# SiLPA_LVDS_IFC.net
KiCad netlist of a schematic drawn in Altium Designer
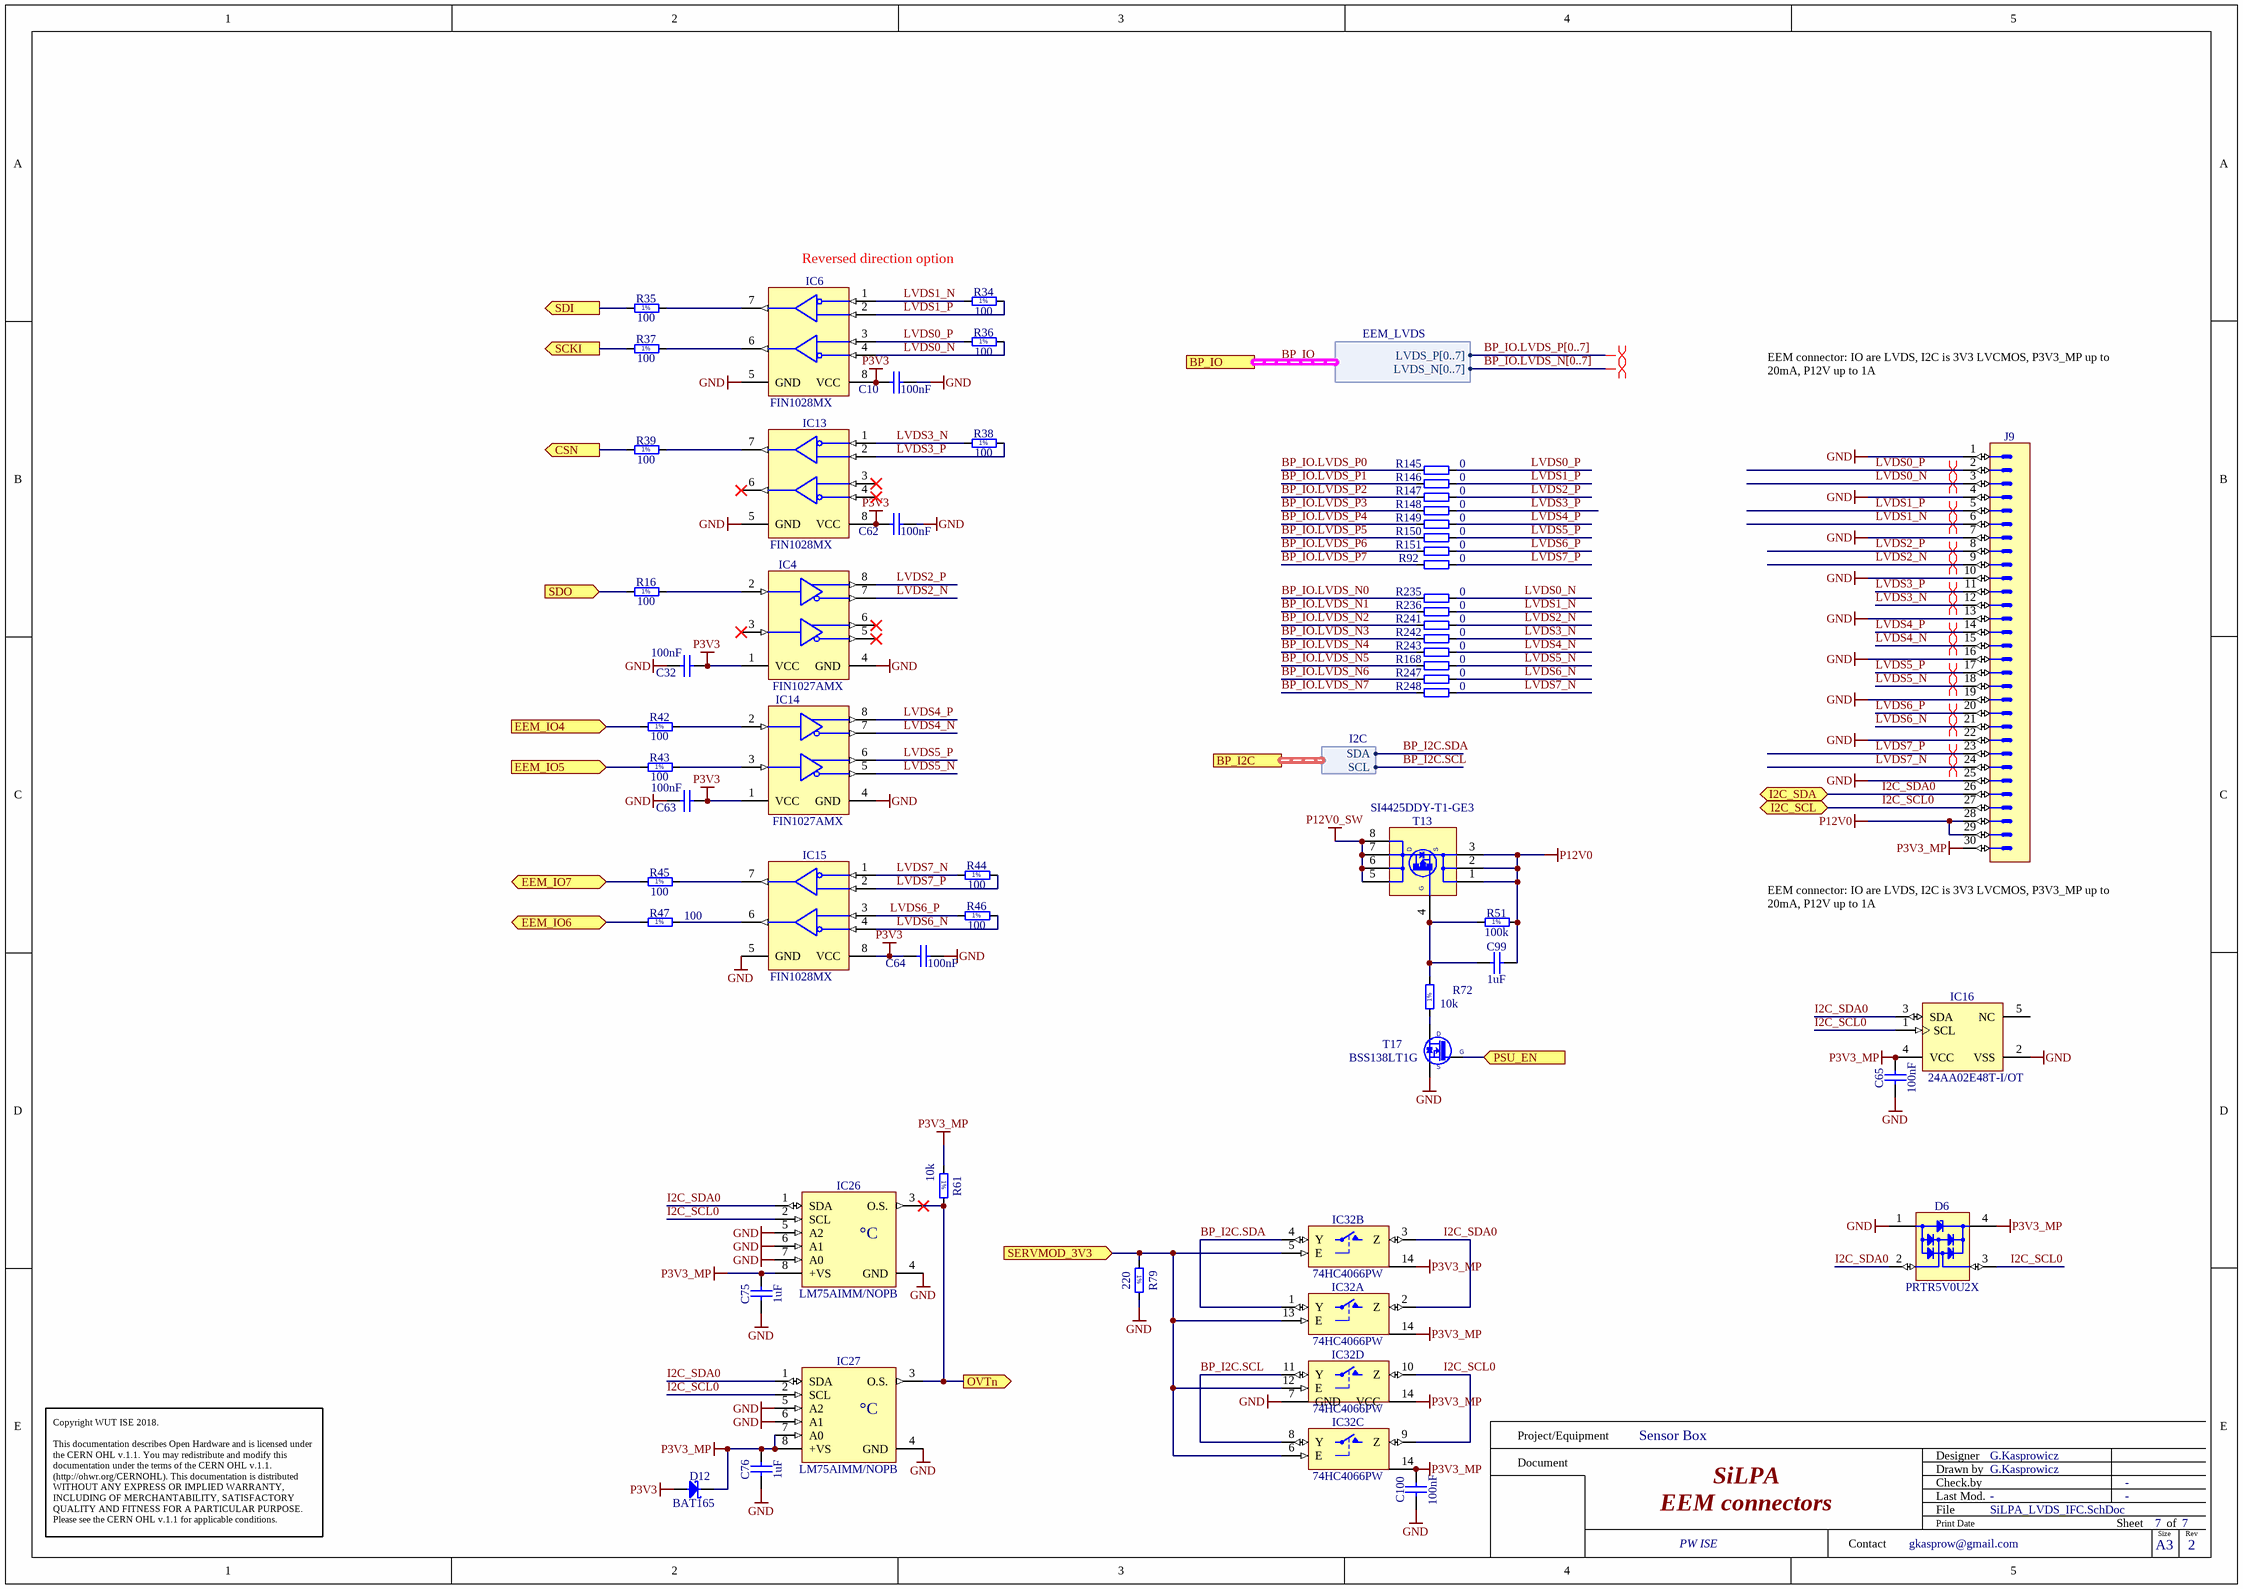
[diagram p0: SiLPA_LVDS_IFC.SchDoc]

(export (version "E")
  (design (tool "Eeschema 10.0.6"))
  (components
    (comp (ref "C10")
      (value "100nF")
      (footprint "CAPC1005X55N")
      (description "Non-polarised capacitor")
      (fields
        (field (name "PART NUMBER") "CC0402_100NF_16V_10%_X5R")
        (field (name "VOLTAGE") "16V")
        (field (name "AUTHOR") "CERN DEM JLC")
      )
      (libsource (lib "Capacitors") (part "Capacitor - non polarized"))
    )
    (comp (ref "C32")
      (value "100nF")
      (footprint "CAPC1005X55N")
      (description "Non-polarised capacitor")
      (fields
        (field (name "PART NUMBER") "CC0402_100NF_16V_10%_X5R")
        (field (name "VOLTAGE") "16V")
        (field (name "AUTHOR") "CERN DEM JLC")
      )
      (libsource (lib "Capacitors") (part "Capacitor - non polarized"))
    )
    (comp (ref "C62")
      (value "100nF")
      (footprint "CAPC1005X55N")
      (description "Non-polarised capacitor")
      (fields
        (field (name "PART NUMBER") "CC0402_100NF_16V_10%_X5R")
        (field (name "VOLTAGE") "16V")
        (field (name "AUTHOR") "CERN DEM JLC")
      )
      (libsource (lib "Capacitors") (part "Capacitor - non polarized"))
    )
    (comp (ref "C63")
      (value "100nF")
      (footprint "CAPC1005X55N")
      (description "Non-polarised capacitor")
      (fields
        (field (name "PART NUMBER") "CC0402_100NF_16V_10%_X5R")
        (field (name "VOLTAGE") "16V")
        (field (name "AUTHOR") "CERN DEM JLC")
      )
      (libsource (lib "Capacitors") (part "Capacitor - non polarized"))
    )
    (comp (ref "C64")
      (value "100nF")
      (footprint "CAPC1005X55N")
      (description "Non-polarised capacitor")
      (fields
        (field (name "PART NUMBER") "CC0402_100NF_16V_10%_X5R")
        (field (name "VOLTAGE") "16V")
        (field (name "AUTHOR") "CERN DEM JLC")
      )
      (libsource (lib "Capacitors") (part "Capacitor - non polarized"))
    )
    (comp (ref "C65")
      (value "100nF")
      (footprint "CAPC1005X55N")
      (description "Non-polarised capacitor")
      (fields
        (field (name "PART NUMBER") "CC0402_100NF_16V_10%_X5R")
        (field (name "VOLTAGE") "16V")
        (field (name "AUTHOR") "CERN DEM JLC")
      )
      (libsource (lib "Capacitors") (part "Capacitor - non polarized"))
    )
    (comp (ref "C75")
      (value "1uF")
      (footprint "CAPC1005X55N")
      (description "Non-polarised capacitor")
      (fields
        (field (name "PART NUMBER") "CC0402_1UF_16V_10%_X5R")
        (field (name "VOLTAGE") "16V")
        (field (name "AUTHOR") "CERN DEM JLC")
      )
      (libsource (lib "Capacitors") (part "Capacitor - non polarized"))
    )
    (comp (ref "C76")
      (value "1uF")
      (footprint "CAPC1005X55N")
      (description "Non-polarised capacitor")
      (fields
        (field (name "PART NUMBER") "CC0402_1UF_16V_10%_X5R")
        (field (name "VOLTAGE") "16V")
        (field (name "AUTHOR") "CERN DEM JLC")
      )
      (libsource (lib "Capacitors") (part "Capacitor - non polarized"))
    )
    (comp (ref "C99")
      (value "1uF")
      (footprint "CAPC1005X55N")
      (description "Non-polarised capacitor")
      (fields
        (field (name "PART NUMBER") "CC0402_1UF_16V_10%_X5R")
        (field (name "VOLTAGE") "16V")
        (field (name "AUTHOR") "CERN DEM JLC")
      )
      (libsource (lib "Capacitors") (part "Capacitor - non polarized"))
    )
    (comp (ref "C100")
      (value "100nF")
      (footprint "CAPC1005X55N")
      (description "Non-polarised capacitor")
      (fields
        (field (name "PART NUMBER") "CC0402_100NF_16V_10%_X5R")
        (field (name "VOLTAGE") "16V")
        (field (name "AUTHOR") "CERN DEM JLC")
      )
      (libsource (lib "EEM_FMC_Carrier") (part "Capacitor - non polarized"))
    )
    (comp (ref "D6")
      (value "PRTR5V0U2X")
      (footprint "SOT190P230X110-4N")
      (description "Ultra Low Capacitance Double Rail-to-Rail ESD Protection Diode")
      (fields
        (field (name "VOLTAGE") "5.5V")
        (field (name "MANUFACTURER") "NXP SEMICONDUCTORS")
        (field (name "AUTHOR") "CERN DEM JLC")
      )
      (libsource (lib "ICs And Semiconductors") (part "PRTR5V0U2X"))
    )
    (comp (ref "D12")
      (value "BAT165")
      (footprint "SOD2512X110N")
      (description "Schottky Diode")
      (fields
        (field (name "VOLTAGE") "40V")
        (field (name "POWER") "750mA")
        (field (name "AUTHOR") "CERN DEM JLC")
      )
      (libsource (lib "ICs And Semiconductors") (part "Diode Schottky"))
    )
    (comp (ref "IC4")
      (value "FIN1027AMX")
      (footprint "SOIC127P600X175-8N")
      (description "3.3V LVDS, 2-Bit, High-Speed, Differential Driver")
      (fields (field (name "MANUFACTURER") "ON Semiconductor") (field (name "AUTHOR") "GK"))
      (libsource (lib "LIBRARY_SCH") (part "IFC_FIN1027A"))
    )
    (comp (ref "IC6")
      (value "FIN1028MX")
      (footprint "SOIC127P600X175-8N")
      (description "3.3V LVDS 2-Bit High-Speed Differential Reciever")
      (fields (field (name "MANUFACTURER") "ON Semiconductor") (field (name "AUTHOR") "GK"))
      (libsource (lib "LIBRARY_SCH") (part "IFC_FIN1028"))
    )
    (comp (ref "IC13")
      (value "FIN1028MX")
      (footprint "SOIC127P600X175-8N")
      (description "3.3V LVDS 2-Bit High-Speed Differential Reciever")
      (fields (field (name "MANUFACTURER") "ON Semiconductor") (field (name "AUTHOR") "GK"))
      (libsource (lib "LIBRARY_SCH") (part "IFC_FIN1028"))
    )
    (comp (ref "IC14")
      (value "FIN1027AMX")
      (footprint "SOIC127P600X175-8N")
      (description "3.3V LVDS, 2-Bit, High-Speed, Differential Driver")
      (fields (field (name "MANUFACTURER") "ON Semiconductor") (field (name "AUTHOR") "GK"))
      (libsource (lib "LIBRARY_SCH") (part "IFC_FIN1027A"))
    )
    (comp (ref "IC15")
      (value "FIN1028MX")
      (footprint "SOIC127P600X175-8N")
      (description "3.3V LVDS 2-Bit High-Speed Differential Reciever")
      (fields (field (name "MANUFACTURER") "ON Semiconductor") (field (name "AUTHOR") "GK"))
      (libsource (lib "LIBRARY_SCH") (part "IFC_FIN1028"))
    )
    (comp (ref "IC16")
      (value "24AA02E48T-I/OT")
      (footprint "SOT95P280X145-5N")
      (description "1.7V-5.5V, 2K I2C Serial EEPROM With EUI-48 Node Identity")
      (fields (field (name "MANUFACTURER") "MICROCHIP TECHNOLOGY") (field (name "AUTHOR") "CERN DEM MR"))
      (libsource (lib "ICs And Semiconductors") (part "24AA02E48T-I/OT"))
    )
    (comp (ref "IC26")
      (value "LM75AIMM/NOPB")
      (footprint "SOP65P490X109-8N")
      (description "Digital Temperature Sensor and Thermal Watchdog with Two-Wire Interface")
      (fields (field (name "MANUFACTURER") "TEXAS INSTRUMENTS") (field (name "AUTHOR") "CERN DEM JLC"))
      (libsource (lib "ICs And Semiconductors") (part "LM75"))
    )
    (comp (ref "IC27")
      (value "LM75AIMM/NOPB")
      (footprint "SOP65P490X109-8N")
      (description "Digital Temperature Sensor and Thermal Watchdog with Two-Wire Interface")
      (fields (field (name "MANUFACTURER") "TEXAS INSTRUMENTS") (field (name "AUTHOR") "CERN DEM JLC"))
      (libsource (lib "ICs And Semiconductors") (part "LM75"))
    )
    (comp (ref "IC32")
      (value "74HC4066PW")
      (footprint "SOP65P640X110-14N")
      (fields (field (name "MANUFACTURER") "NXP SEMICONDUCTORS") (field (name "AUTHOR") "CERN DEM JLC"))
      (libsource (lib "EEM_FMC_Carrier") (part "4066"))
    )
    (comp (ref "J9")
      (value "~")
      (footprint "3M_N2530-6002RB")
      (description "Connector 30 Male")
      (fields
        (field (name "PART NUMBER") "3M_N2530-6002RB")
        (field (name "MANUFACTURER") "3M")
        (field (name "AUTHOR") "CERN DEM JLC")
      )
      (libsource (lib "Connectors") (part "Connector 30 Male"))
    )
    (comp (ref "R16")
      (value "100")
      (footprint "RESC1005X40N")
      (description "Resistor - 1%")
      (fields
        (field (name "PART NUMBER") "R0402_100R_1%_0.0625W_100PPM")
        (field (name "POWER") "0.0625W")
        (field (name "AUTHOR") "CERN DEM JLC")
      )
      (libsource (lib "Resistors") (part "Resistor - 1%"))
    )
    (comp (ref "R34")
      (value "100")
      (footprint "RESC1005X40N")
      (description "Resistor - 1%")
      (fields
        (field (name "PART NUMBER") "R0402_100R_1%_0.0625W_100PPM")
        (field (name "POWER") "0.0625W")
        (field (name "AUTHOR") "CERN DEM JLC")
      )
      (libsource (lib "Resistors") (part "Resistor - 1%"))
    )
    (comp (ref "R35")
      (value "100")
      (footprint "RESC1005X40N")
      (description "Resistor - 1%")
      (fields
        (field (name "PART NUMBER") "R0402_100R_1%_0.0625W_100PPM")
        (field (name "POWER") "0.0625W")
        (field (name "AUTHOR") "CERN DEM JLC")
      )
      (libsource (lib "Resistors") (part "Resistor - 1%"))
    )
    (comp (ref "R36")
      (value "100")
      (footprint "RESC1005X40N")
      (description "Resistor - 1%")
      (fields
        (field (name "PART NUMBER") "R0402_100R_1%_0.0625W_100PPM")
        (field (name "POWER") "0.0625W")
        (field (name "AUTHOR") "CERN DEM JLC")
      )
      (libsource (lib "Resistors") (part "Resistor - 1%"))
    )
    (comp (ref "R37")
      (value "100")
      (footprint "RESC1005X40N")
      (description "Resistor - 1%")
      (fields
        (field (name "PART NUMBER") "R0402_100R_1%_0.0625W_100PPM")
        (field (name "POWER") "0.0625W")
        (field (name "AUTHOR") "CERN DEM JLC")
      )
      (libsource (lib "Resistors") (part "Resistor - 1%"))
    )
    (comp (ref "R38")
      (value "100")
      (footprint "RESC1005X40N")
      (description "Resistor - 1%")
      (fields
        (field (name "PART NUMBER") "R0402_100R_1%_0.0625W_100PPM")
        (field (name "POWER") "0.0625W")
        (field (name "AUTHOR") "CERN DEM JLC")
      )
      (libsource (lib "Resistors") (part "Resistor - 1%"))
    )
    (comp (ref "R39")
      (value "100")
      (footprint "RESC1005X40N")
      (description "Resistor - 1%")
      (fields
        (field (name "PART NUMBER") "R0402_100R_1%_0.0625W_100PPM")
        (field (name "POWER") "0.0625W")
        (field (name "AUTHOR") "CERN DEM JLC")
      )
      (libsource (lib "Resistors") (part "Resistor - 1%"))
    )
    (comp (ref "R42")
      (value "100")
      (footprint "RESC1005X40N")
      (description "Resistor - 1%")
      (fields
        (field (name "PART NUMBER") "R0402_100R_1%_0.0625W_100PPM")
        (field (name "POWER") "0.0625W")
        (field (name "AUTHOR") "CERN DEM JLC")
      )
      (libsource (lib "Resistors") (part "Resistor - 1%"))
    )
    (comp (ref "R43")
      (value "100")
      (footprint "RESC1005X40N")
      (description "Resistor - 1%")
      (fields
        (field (name "PART NUMBER") "R0402_100R_1%_0.0625W_100PPM")
        (field (name "POWER") "0.0625W")
        (field (name "AUTHOR") "CERN DEM JLC")
      )
      (libsource (lib "Resistors") (part "Resistor - 1%"))
    )
    (comp (ref "R44")
      (value "100")
      (footprint "RESC1005X40N")
      (description "Resistor - 1%")
      (fields
        (field (name "PART NUMBER") "R0402_100R_1%_0.0625W_100PPM")
        (field (name "POWER") "0.0625W")
        (field (name "AUTHOR") "CERN DEM JLC")
      )
      (libsource (lib "Resistors") (part "Resistor - 1%"))
    )
    (comp (ref "R45")
      (value "100")
      (footprint "RESC1005X40N")
      (description "Resistor - 1%")
      (fields
        (field (name "PART NUMBER") "R0402_100R_1%_0.0625W_100PPM")
        (field (name "POWER") "0.0625W")
        (field (name "AUTHOR") "CERN DEM JLC")
      )
      (libsource (lib "Resistors") (part "Resistor - 1%"))
    )
    (comp (ref "R46")
      (value "100")
      (footprint "RESC1005X40N")
      (description "Resistor - 1%")
      (fields
        (field (name "PART NUMBER") "R0402_100R_1%_0.0625W_100PPM")
        (field (name "POWER") "0.0625W")
        (field (name "AUTHOR") "CERN DEM JLC")
      )
      (libsource (lib "Resistors") (part "Resistor - 1%"))
    )
    (comp (ref "R47")
      (value "100")
      (footprint "RESC1005X40N")
      (description "Resistor - 1%")
      (fields
        (field (name "PART NUMBER") "R0402_100R_1%_0.0625W_100PPM")
        (field (name "POWER") "0.0625W")
        (field (name "AUTHOR") "CERN DEM JLC")
      )
      (libsource (lib "Resistors") (part "Resistor - 1%"))
    )
    (comp (ref "R51")
      (value "100k")
      (footprint "RESC1608X55N")
      (description "Resistor - 1%")
      (fields
        (field (name "PART NUMBER") "R0603_100K_1%_0.1W_100PPM")
        (field (name "POWER") "0.1W")
        (field (name "AUTHOR") "CERN DEM JLC")
      )
      (libsource (lib "Resistors") (part "Resistor - 1%"))
    )
    (comp (ref "R61")
      (value "10k")
      (footprint "RESC1005X40N")
      (description "Resistor - 1%")
      (fields
        (field (name "PART NUMBER") "R0402_10K_1%_0.0625W_100PPM")
        (field (name "POWER") "0.0625W")
        (field (name "AUTHOR") "CERN DEM JLC")
      )
      (libsource (lib "Resistors") (part "Resistor - 1%"))
    )
    (comp (ref "R72")
      (value "10k")
      (footprint "RESC1005X40N")
      (description "Resistor - 1%")
      (fields
        (field (name "PART NUMBER") "R0402_10K_1%_0.0625W_100PPM")
        (field (name "POWER") "0.0625W")
        (field (name "AUTHOR") "CERN DEM JLC")
      )
      (libsource (lib "Resistors") (part "Resistor - 1%"))
    )
    (comp (ref "R79")
      (value "220")
      (footprint "RESC1005X40N")
      (description "Resistor - 1%")
      (fields
        (field (name "PART NUMBER") "R0402_10K_1%_0.0625W_100PPM")
        (field (name "POWER") "0.0625W")
        (field (name "AUTHOR") "CERN DEM JLC")
      )
      (libsource (lib "Resistors") (part "Resistor - 1%"))
    )
    (comp (ref "R92")
      (value "0")
      (footprint "RESC1005X40N")
      (description "Resistor")
      (fields
        (field (name "PART NUMBER") "R0402_0R_JUMPER")
        (field (name "MANUFACTURER") "GENERIC")
        (field (name "AUTHOR") "CERN DEM JLC")
      )
      (libsource (lib "Resistors") (part "Resistor"))
    )
    (comp (ref "R145")
      (value "0")
      (footprint "RESC1005X40N")
      (description "Resistor")
      (fields
        (field (name "PART NUMBER") "R0402_0R_JUMPER")
        (field (name "MANUFACTURER") "GENERIC")
        (field (name "AUTHOR") "CERN DEM JLC")
      )
      (libsource (lib "Resistors") (part "Resistor"))
    )
    (comp (ref "R146")
      (value "0")
      (footprint "RESC1005X40N")
      (description "Resistor")
      (fields
        (field (name "PART NUMBER") "R0402_0R_JUMPER")
        (field (name "MANUFACTURER") "GENERIC")
        (field (name "AUTHOR") "CERN DEM JLC")
      )
      (libsource (lib "Resistors") (part "Resistor"))
    )
    (comp (ref "R147")
      (value "0")
      (footprint "RESC1005X40N")
      (description "Resistor")
      (fields
        (field (name "PART NUMBER") "R0402_0R_JUMPER")
        (field (name "MANUFACTURER") "GENERIC")
        (field (name "AUTHOR") "CERN DEM JLC")
      )
      (libsource (lib "Resistors") (part "Resistor"))
    )
    (comp (ref "R148")
      (value "0")
      (footprint "RESC1005X40N")
      (description "Resistor")
      (fields
        (field (name "PART NUMBER") "R0402_0R_JUMPER")
        (field (name "MANUFACTURER") "GENERIC")
        (field (name "AUTHOR") "CERN DEM JLC")
      )
      (libsource (lib "Resistors") (part "Resistor"))
    )
    (comp (ref "R149")
      (value "0")
      (footprint "RESC1005X40N")
      (description "Resistor")
      (fields
        (field (name "PART NUMBER") "R0402_0R_JUMPER")
        (field (name "MANUFACTURER") "GENERIC")
        (field (name "AUTHOR") "CERN DEM JLC")
      )
      (libsource (lib "Resistors") (part "Resistor"))
    )
    (comp (ref "R150")
      (value "0")
      (footprint "RESC1005X40N")
      (description "Resistor")
      (fields
        (field (name "PART NUMBER") "R0402_0R_JUMPER")
        (field (name "MANUFACTURER") "GENERIC")
        (field (name "AUTHOR") "CERN DEM JLC")
      )
      (libsource (lib "Resistors") (part "Resistor"))
    )
    (comp (ref "R151")
      (value "0")
      (footprint "RESC1005X40N")
      (description "Resistor")
      (fields
        (field (name "PART NUMBER") "R0402_0R_JUMPER")
        (field (name "MANUFACTURER") "GENERIC")
        (field (name "AUTHOR") "CERN DEM JLC")
      )
      (libsource (lib "Resistors") (part "Resistor"))
    )
    (comp (ref "R168")
      (value "0")
      (footprint "RESC1005X40N")
      (description "Resistor")
      (fields
        (field (name "PART NUMBER") "R0402_0R_JUMPER")
        (field (name "MANUFACTURER") "GENERIC")
        (field (name "AUTHOR") "CERN DEM JLC")
      )
      (libsource (lib "Resistors") (part "Resistor"))
    )
    (comp (ref "R235")
      (value "0")
      (footprint "RESC1005X40N")
      (description "Resistor")
      (fields
        (field (name "PART NUMBER") "R0402_0R_JUMPER")
        (field (name "MANUFACTURER") "GENERIC")
        (field (name "AUTHOR") "CERN DEM JLC")
      )
      (libsource (lib "Resistors") (part "Resistor"))
    )
    (comp (ref "R236")
      (value "0")
      (footprint "RESC1005X40N")
      (description "Resistor")
      (fields
        (field (name "PART NUMBER") "R0402_0R_JUMPER")
        (field (name "MANUFACTURER") "GENERIC")
        (field (name "AUTHOR") "CERN DEM JLC")
      )
      (libsource (lib "Resistors") (part "Resistor"))
    )
    (comp (ref "R241")
      (value "0")
      (footprint "RESC1005X40N")
      (description "Resistor")
      (fields
        (field (name "PART NUMBER") "R0402_0R_JUMPER")
        (field (name "MANUFACTURER") "GENERIC")
        (field (name "AUTHOR") "CERN DEM JLC")
      )
      (libsource (lib "Resistors") (part "Resistor"))
    )
    (comp (ref "R242")
      (value "0")
      (footprint "RESC1005X40N")
      (description "Resistor")
      (fields
        (field (name "PART NUMBER") "R0402_0R_JUMPER")
        (field (name "MANUFACTURER") "GENERIC")
        (field (name "AUTHOR") "CERN DEM JLC")
      )
      (libsource (lib "Resistors") (part "Resistor"))
    )
    (comp (ref "R243")
      (value "0")
      (footprint "RESC1005X40N")
      (description "Resistor")
      (fields
        (field (name "PART NUMBER") "R0402_0R_JUMPER")
        (field (name "MANUFACTURER") "GENERIC")
        (field (name "AUTHOR") "CERN DEM JLC")
      )
      (libsource (lib "Resistors") (part "Resistor"))
    )
    (comp (ref "R247")
      (value "0")
      (footprint "RESC1005X40N")
      (description "Resistor")
      (fields
        (field (name "PART NUMBER") "R0402_0R_JUMPER")
        (field (name "MANUFACTURER") "GENERIC")
        (field (name "AUTHOR") "CERN DEM JLC")
      )
      (libsource (lib "Resistors") (part "Resistor"))
    )
    (comp (ref "R248")
      (value "0")
      (footprint "RESC1005X40N")
      (description "Resistor")
      (fields
        (field (name "PART NUMBER") "R0402_0R_JUMPER")
        (field (name "MANUFACTURER") "GENERIC")
        (field (name "AUTHOR") "CERN DEM JLC")
      )
      (libsource (lib "Resistors") (part "Resistor"))
    )
    (comp (ref "T13")
      (value "SI4425DDY-T1-GE3")
      (footprint "SOIC127P600X175-8N")
      (description "-30V -19.7A P-Channel MOSFET")
      (fields (field (name "MANUFACTURER") "VISHAY SILICONIX") (field (name "AUTHOR") "CERN DEM MR"))
      (libsource (lib "ICs And Semiconductors") (part "SI4425DDY"))
    )
    (comp (ref "T17")
      (value "BSS138LT1G")
      (footprint "SOT95P240X110-3N")
      (description "N-CHANNEL MOSFET WITH DIODE")
      (fields (field (name "MANUFACTURER") "ON SEMICONDUCTOR") (field (name "AUTHOR") "CERN DEM JLC"))
      (libsource (lib "ICs And Semiconductors") (part "N-MOSFET-D 1G 2S 3D"))
    )
  )
  (nets
    (net (code "3") (name "/BP_I2C.SCL") (class "Default")
      (node (ref "IC32") (pin "11") (pinfunction "Y_11") (pintype "bidirectional"))
      (node (ref "IC32") (pin "8") (pinfunction "Y_8") (pintype "bidirectional"))
    )
    (net (code "4") (name "/BP_I2C.SDA") (class "Default")
      (node (ref "IC32") (pin "1") (pinfunction "Y_1") (pintype "bidirectional"))
      (node (ref "IC32") (pin "4") (pinfunction "Y_4") (pintype "bidirectional"))
    )
    (net (code "5") (name "/BP_IO.LVDS_N0") (class "Default")
      (node (ref "R235") (pin "1") (pinfunction "1_1") (pintype "passive"))
    )
    (net (code "6") (name "/BP_IO.LVDS_N1") (class "Default")
      (node (ref "R236") (pin "1") (pinfunction "1_1") (pintype "passive"))
    )
    (net (code "7") (name "/BP_IO.LVDS_N2") (class "Default")
      (node (ref "R241") (pin "1") (pinfunction "1_1") (pintype "passive"))
    )
    (net (code "8") (name "/BP_IO.LVDS_N3") (class "Default")
      (node (ref "R242") (pin "1") (pinfunction "1_1") (pintype "passive"))
    )
    (net (code "9") (name "/BP_IO.LVDS_N4") (class "Default")
      (node (ref "R243") (pin "1") (pinfunction "1_1") (pintype "passive"))
    )
    (net (code "10") (name "/BP_IO.LVDS_N5") (class "Default")
      (node (ref "R168") (pin "1") (pinfunction "1_1") (pintype "passive"))
    )
    (net (code "11") (name "/BP_IO.LVDS_N6") (class "Default")
      (node (ref "R247") (pin "1") (pinfunction "1_1") (pintype "passive"))
    )
    (net (code "12") (name "/BP_IO.LVDS_N7") (class "Default")
      (node (ref "R248") (pin "1") (pinfunction "1_1") (pintype "passive"))
    )
    (net (code "14") (name "/BP_IO.LVDS_P0") (class "Default")
      (node (ref "R145") (pin "1") (pinfunction "1_1") (pintype "passive"))
    )
    (net (code "15") (name "/BP_IO.LVDS_P1") (class "Default")
      (node (ref "R146") (pin "1") (pinfunction "1_1") (pintype "passive"))
    )
    (net (code "16") (name "/BP_IO.LVDS_P2") (class "Default")
      (node (ref "R147") (pin "1") (pinfunction "1_1") (pintype "passive"))
    )
    (net (code "17") (name "/BP_IO.LVDS_P3") (class "Default")
      (node (ref "R148") (pin "1") (pinfunction "1_1") (pintype "passive"))
    )
    (net (code "18") (name "/BP_IO.LVDS_P4") (class "Default")
      (node (ref "R149") (pin "1") (pinfunction "1_1") (pintype "passive"))
    )
    (net (code "19") (name "/BP_IO.LVDS_P5") (class "Default")
      (node (ref "R150") (pin "1") (pinfunction "1_1") (pintype "passive"))
    )
    (net (code "20") (name "/BP_IO.LVDS_P6") (class "Default")
      (node (ref "R151") (pin "1") (pinfunction "1_1") (pintype "passive"))
    )
    (net (code "21") (name "/BP_IO.LVDS_P7") (class "Default")
      (node (ref "R92") (pin "1") (pinfunction "1_1") (pintype "passive"))
    )
    (net (code "22") (name "/CSN") (class "Default")
      (node (ref "R39") (pin "1") (pinfunction "1_1") (pintype "passive"))
    )
    (net (code "23") (name "/EEM_IO4") (class "Default")
      (node (ref "R42") (pin "1") (pinfunction "1_1") (pintype "passive"))
    )
    (net (code "24") (name "/EEM_IO5") (class "Default")
      (node (ref "R43") (pin "1") (pinfunction "1_1") (pintype "passive"))
    )
    (net (code "25") (name "/EEM_IO6") (class "Default")
      (node (ref "R47") (pin "1") (pinfunction "1_1") (pintype "passive"))
    )
    (net (code "26") (name "/EEM_IO7") (class "Default")
      (node (ref "R45") (pin "1") (pinfunction "1_1") (pintype "passive"))
    )
    (net (code "27") (name "/I2C_SCL0") (class "Default")
      (node (ref "D6") (pin "3") (pinfunction "I/O2_3") (pintype "bidirectional"))
      (node (ref "IC16") (pin "1") (pinfunction "SCL_1") (pintype "input"))
      (node (ref "IC26") (pin "2") (pinfunction "SCL_2") (pintype "input"))
      (node (ref "IC27") (pin "2") (pinfunction "SCL_2") (pintype "input"))
      (node (ref "IC32") (pin "10") (pinfunction "Z_10") (pintype "bidirectional"))
      (node (ref "IC32") (pin "9") (pinfunction "Z_9") (pintype "bidirectional"))
      (node (ref "J9") (pin "27") (pinfunction "27_27") (pintype "bidirectional"))
    )
    (net (code "28") (name "/I2C_SDA0") (class "Default")
      (node (ref "D6") (pin "2") (pinfunction "I/O1_2") (pintype "bidirectional"))
      (node (ref "IC16") (pin "3") (pinfunction "SDA_3") (pintype "bidirectional"))
      (node (ref "IC26") (pin "1") (pinfunction "SDA_1") (pintype "bidirectional"))
      (node (ref "IC27") (pin "1") (pinfunction "SDA_1") (pintype "bidirectional"))
      (node (ref "IC32") (pin "2") (pinfunction "Z_2") (pintype "bidirectional"))
      (node (ref "IC32") (pin "3") (pinfunction "Z_3") (pintype "bidirectional"))
      (node (ref "J9") (pin "26") (pinfunction "26_26") (pintype "bidirectional"))
    )
    (net (code "29") (name "/LVDS0_N") (class "Default")
      (node (ref "IC6") (pin "4") (pinfunction "RIN2-_4") (pintype "input"))
      (node (ref "J9") (pin "3") (pinfunction "3_3") (pintype "bidirectional"))
      (node (ref "R235") (pin "2") (pinfunction "2_2") (pintype "passive"))
      (node (ref "R36") (pin "2") (pinfunction "2_2") (pintype "passive"))
    )
    (net (code "30") (name "/LVDS0_P") (class "Default")
      (node (ref "IC6") (pin "3") (pinfunction "RIN2+_3") (pintype "input"))
      (node (ref "J9") (pin "2") (pinfunction "2_2") (pintype "bidirectional"))
      (node (ref "R145") (pin "2") (pinfunction "2_2") (pintype "passive"))
      (node (ref "R36") (pin "1") (pinfunction "1_1") (pintype "passive"))
    )
    (net (code "31") (name "/LVDS1_N") (class "Default")
      (node (ref "IC6") (pin "1") (pinfunction "RIN1-_1") (pintype "input"))
      (node (ref "J9") (pin "6") (pinfunction "6_6") (pintype "bidirectional"))
      (node (ref "R236") (pin "2") (pinfunction "2_2") (pintype "passive"))
      (node (ref "R34") (pin "1") (pinfunction "1_1") (pintype "passive"))
    )
    (net (code "32") (name "/LVDS1_P") (class "Default")
      (node (ref "IC6") (pin "2") (pinfunction "RIN1+_2") (pintype "input"))
      (node (ref "J9") (pin "5") (pinfunction "5_5") (pintype "bidirectional"))
      (node (ref "R146") (pin "2") (pinfunction "2_2") (pintype "passive"))
      (node (ref "R34") (pin "2") (pinfunction "2_2") (pintype "passive"))
    )
    (net (code "33") (name "/LVDS2_N") (class "Default")
      (node (ref "IC4") (pin "7") (pinfunction "DOUT-_7") (pintype "output"))
      (node (ref "J9") (pin "9") (pinfunction "9_9") (pintype "bidirectional"))
      (node (ref "R241") (pin "2") (pinfunction "2_2") (pintype "passive"))
    )
    (net (code "34") (name "/LVDS2_P") (class "Default")
      (node (ref "IC4") (pin "8") (pinfunction "DOUT+_8") (pintype "output"))
      (node (ref "J9") (pin "8") (pinfunction "8_8") (pintype "bidirectional"))
      (node (ref "R147") (pin "2") (pinfunction "2_2") (pintype "passive"))
    )
    (net (code "35") (name "/LVDS3_N") (class "Default")
      (node (ref "IC13") (pin "1") (pinfunction "RIN1-_1") (pintype "input"))
      (node (ref "J9") (pin "12") (pinfunction "12_12") (pintype "bidirectional"))
      (node (ref "R242") (pin "2") (pinfunction "2_2") (pintype "passive"))
      (node (ref "R38") (pin "1") (pinfunction "1_1") (pintype "passive"))
    )
    (net (code "36") (name "/LVDS3_P") (class "Default")
      (node (ref "IC13") (pin "2") (pinfunction "RIN1+_2") (pintype "input"))
      (node (ref "J9") (pin "11") (pinfunction "11_11") (pintype "bidirectional"))
      (node (ref "R148") (pin "2") (pinfunction "2_2") (pintype "passive"))
      (node (ref "R38") (pin "2") (pinfunction "2_2") (pintype "passive"))
    )
    (net (code "37") (name "/LVDS4_N") (class "Default")
      (node (ref "IC14") (pin "7") (pinfunction "DOUT-_7") (pintype "output"))
      (node (ref "J9") (pin "15") (pinfunction "15_15") (pintype "bidirectional"))
      (node (ref "R243") (pin "2") (pinfunction "2_2") (pintype "passive"))
    )
    (net (code "38") (name "/LVDS4_P") (class "Default")
      (node (ref "IC14") (pin "8") (pinfunction "DOUT+_8") (pintype "output"))
      (node (ref "J9") (pin "14") (pinfunction "14_14") (pintype "bidirectional"))
      (node (ref "R149") (pin "2") (pinfunction "2_2") (pintype "passive"))
    )
    (net (code "39") (name "/LVDS5_N") (class "Default")
      (node (ref "IC14") (pin "5") (pinfunction "DOUT-_5") (pintype "output"))
      (node (ref "J9") (pin "18") (pinfunction "18_18") (pintype "bidirectional"))
      (node (ref "R168") (pin "2") (pinfunction "2_2") (pintype "passive"))
    )
    (net (code "40") (name "/LVDS5_P") (class "Default")
      (node (ref "IC14") (pin "6") (pinfunction "DOUT+_6") (pintype "output"))
      (node (ref "J9") (pin "17") (pinfunction "17_17") (pintype "bidirectional"))
      (node (ref "R150") (pin "2") (pinfunction "2_2") (pintype "passive"))
    )
    (net (code "41") (name "/LVDS6_N") (class "Default")
      (node (ref "IC15") (pin "4") (pinfunction "RIN2-_4") (pintype "input"))
      (node (ref "J9") (pin "21") (pinfunction "21_21") (pintype "bidirectional"))
      (node (ref "R247") (pin "2") (pinfunction "2_2") (pintype "passive"))
      (node (ref "R46") (pin "2") (pinfunction "2_2") (pintype "passive"))
    )
    (net (code "42") (name "/LVDS6_P") (class "Default")
      (node (ref "IC15") (pin "3") (pinfunction "RIN2+_3") (pintype "input"))
      (node (ref "J9") (pin "20") (pinfunction "20_20") (pintype "bidirectional"))
      (node (ref "R151") (pin "2") (pinfunction "2_2") (pintype "passive"))
      (node (ref "R46") (pin "1") (pinfunction "1_1") (pintype "passive"))
    )
    (net (code "43") (name "/LVDS7_N") (class "Default")
      (node (ref "IC15") (pin "1") (pinfunction "RIN1-_1") (pintype "input"))
      (node (ref "J9") (pin "24") (pinfunction "24_24") (pintype "bidirectional"))
      (node (ref "R248") (pin "2") (pinfunction "2_2") (pintype "passive"))
      (node (ref "R44") (pin "1") (pinfunction "1_1") (pintype "passive"))
    )
    (net (code "44") (name "/LVDS7_P") (class "Default")
      (node (ref "IC15") (pin "2") (pinfunction "RIN1+_2") (pintype "input"))
      (node (ref "J9") (pin "23") (pinfunction "23_23") (pintype "bidirectional"))
      (node (ref "R44") (pin "2") (pinfunction "2_2") (pintype "passive"))
      (node (ref "R92") (pin "2") (pinfunction "2_2") (pintype "passive"))
    )
    (net (code "45") (name "/OVTn") (class "Default")
      (node (ref "IC26") (pin "3") (pinfunction "O.S._3") (pintype "output"))
      (node (ref "IC27") (pin "3") (pinfunction "O.S._3") (pintype "output"))
      (node (ref "R61") (pin "2") (pinfunction "2_2") (pintype "passive"))
    )
    (net (code "46") (name "/PSU_EN") (class "Default")
      (node (ref "T17") (pin "1") (pinfunction "G_1") (pintype "passive"))
    )
    (net (code "47") (name "/SCKI") (class "Default")
      (node (ref "R37") (pin "1") (pinfunction "1_1") (pintype "passive"))
    )
    (net (code "48") (name "/SDI") (class "Default")
      (node (ref "R35") (pin "1") (pinfunction "1_1") (pintype "passive"))
    )
    (net (code "49") (name "/SDO") (class "Default")
      (node (ref "R16") (pin "1") (pinfunction "1_1") (pintype "passive"))
    )
    (net (code "50") (name "/SERVMOD_3V3") (class "Default")
      (node (ref "IC32") (pin "12") (pinfunction "E_12") (pintype "input"))
      (node (ref "IC32") (pin "13") (pinfunction "E_13") (pintype "input"))
      (node (ref "IC32") (pin "5") (pinfunction "E_5") (pintype "input"))
      (node (ref "IC32") (pin "6") (pinfunction "E_6") (pintype "input"))
      (node (ref "R79") (pin "1") (pinfunction "1_1") (pintype "passive"))
    )
    (net (code "54") (name "GND") (class "Default")
      (node (ref "C10") (pin "1") (pinfunction "1_1") (pintype "passive"))
      (node (ref "C100") (pin "1") (pinfunction "1_1") (pintype "passive"))
      (node (ref "C32") (pin "1") (pinfunction "1_1") (pintype "passive"))
      (node (ref "C62") (pin "1") (pinfunction "1_1") (pintype "passive"))
      (node (ref "C63") (pin "1") (pinfunction "1_1") (pintype "passive"))
      (node (ref "C64") (pin "1") (pinfunction "1_1") (pintype "passive"))
      (node (ref "C65") (pin "1") (pinfunction "1_1") (pintype "passive"))
      (node (ref "C75") (pin "1") (pinfunction "1_1") (pintype "passive"))
      (node (ref "C76") (pin "1") (pinfunction "1_1") (pintype "passive"))
      (node (ref "D6") (pin "1") (pinfunction "GND_1") (pintype "power_in"))
      (node (ref "IC13") (pin "5") (pinfunction "GND_5") (pintype "power_in"))
      (node (ref "IC14") (pin "4") (pinfunction "GND_4") (pintype "power_in"))
      (node (ref "IC15") (pin "5") (pinfunction "GND_5") (pintype "power_in"))
      (node (ref "IC16") (pin "2") (pinfunction "VSS_2") (pintype "power_in"))
      (node (ref "IC26") (pin "4") (pinfunction "GND_4") (pintype "power_in"))
      (node (ref "IC26") (pin "5") (pinfunction "A2_5") (pintype "input"))
      (node (ref "IC26") (pin "6") (pinfunction "A1_6") (pintype "input"))
      (node (ref "IC26") (pin "7") (pinfunction "A0_7") (pintype "input"))
      (node (ref "IC27") (pin "4") (pinfunction "GND_4") (pintype "power_in"))
      (node (ref "IC27") (pin "5") (pinfunction "A2_5") (pintype "input"))
      (node (ref "IC27") (pin "6") (pinfunction "A1_6") (pintype "input"))
      (node (ref "IC32") (pin "7") (pinfunction "GND_7") (pintype "power_in"))
      (node (ref "IC4") (pin "4") (pinfunction "GND_4") (pintype "power_in"))
      (node (ref "IC6") (pin "5") (pinfunction "GND_5") (pintype "power_in"))
      (node (ref "J9") (pin "1") (pinfunction "1_1") (pintype "bidirectional"))
      (node (ref "J9") (pin "10") (pinfunction "10_10") (pintype "bidirectional"))
      (node (ref "J9") (pin "13") (pinfunction "13_13") (pintype "bidirectional"))
      (node (ref "J9") (pin "16") (pinfunction "16_16") (pintype "bidirectional"))
      (node (ref "J9") (pin "19") (pinfunction "19_19") (pintype "bidirectional"))
      (node (ref "J9") (pin "22") (pinfunction "22_22") (pintype "bidirectional"))
      (node (ref "J9") (pin "25") (pinfunction "25_25") (pintype "bidirectional"))
      (node (ref "J9") (pin "4") (pinfunction "4_4") (pintype "bidirectional"))
      (node (ref "J9") (pin "7") (pinfunction "7_7") (pintype "bidirectional"))
      (node (ref "R79") (pin "2") (pinfunction "2_2") (pintype "passive"))
      (node (ref "T17") (pin "2") (pinfunction "S_2") (pintype "passive"))
    )
    (net (code "55") (name "Net-(C99-Pad1)") (class "Default")
      (node (ref "C99") (pin "1") (pinfunction "1_1") (pintype "passive"))
      (node (ref "R51") (pin "1") (pinfunction "1_1") (pintype "passive"))
      (node (ref "R72") (pin "2") (pinfunction "2_2") (pintype "passive"))
      (node (ref "T13") (pin "4") (pinfunction "S_4") (pintype "passive"))
    )
    (net (code "56") (name "Net-(IC4-DIN1)") (class "Default")
      (node (ref "IC4") (pin "2") (pinfunction "DIN1_2") (pintype "input"))
      (node (ref "R16") (pin "2") (pinfunction "2_2") (pintype "passive"))
    )
    (net (code "57") (name "Net-(IC6-ROUT1)") (class "Default")
      (node (ref "IC6") (pin "7") (pinfunction "ROUT1_7") (pintype "output"))
      (node (ref "R35") (pin "2") (pinfunction "2_2") (pintype "passive"))
    )
    (net (code "58") (name "Net-(IC6-ROUT2)") (class "Default")
      (node (ref "IC6") (pin "6") (pinfunction "ROUT2_6") (pintype "output"))
      (node (ref "R37") (pin "2") (pinfunction "2_2") (pintype "passive"))
    )
    (net (code "59") (name "Net-(IC13-ROUT1)") (class "Default")
      (node (ref "IC13") (pin "7") (pinfunction "ROUT1_7") (pintype "output"))
      (node (ref "R39") (pin "2") (pinfunction "2_2") (pintype "passive"))
    )
    (net (code "60") (name "Net-(IC14-DIN1)") (class "Default")
      (node (ref "IC14") (pin "2") (pinfunction "DIN1_2") (pintype "input"))
      (node (ref "R42") (pin "2") (pinfunction "2_2") (pintype "passive"))
    )
    (net (code "61") (name "Net-(IC14-DIN2RIN-)") (class "Default")
      (node (ref "IC14") (pin "3") (pinfunction "DIN2RIN-_3") (pintype "input"))
      (node (ref "R43") (pin "2") (pinfunction "2_2") (pintype "passive"))
    )
    (net (code "62") (name "Net-(IC15-ROUT1)") (class "Default")
      (node (ref "IC15") (pin "7") (pinfunction "ROUT1_7") (pintype "output"))
      (node (ref "R45") (pin "2") (pinfunction "2_2") (pintype "passive"))
    )
    (net (code "63") (name "Net-(IC15-ROUT2)") (class "Default")
      (node (ref "IC15") (pin "6") (pinfunction "ROUT2_6") (pintype "output"))
      (node (ref "R47") (pin "2") (pinfunction "2_2") (pintype "passive"))
    )
    (net (code "64") (name "Net-(T17-D)") (class "Default")
      (node (ref "R72") (pin "1") (pinfunction "1_1") (pintype "passive"))
      (node (ref "T17") (pin "3") (pinfunction "D_3") (pintype "passive"))
    )
    (net (code "65") (name "P3V3") (class "Default")
      (node (ref "C10") (pin "2") (pinfunction "2_2") (pintype "passive"))
      (node (ref "C32") (pin "2") (pinfunction "2_2") (pintype "passive"))
      (node (ref "C62") (pin "2") (pinfunction "2_2") (pintype "passive"))
      (node (ref "C63") (pin "2") (pinfunction "2_2") (pintype "passive"))
      (node (ref "C64") (pin "2") (pinfunction "2_2") (pintype "passive"))
      (node (ref "D12") (pin "2") (pinfunction "A_2") (pintype "passive"))
      (node (ref "IC13") (pin "8") (pinfunction "VCC_8") (pintype "power_in"))
      (node (ref "IC14") (pin "1") (pinfunction "VCC_1") (pintype "power_in"))
      (node (ref "IC15") (pin "8") (pinfunction "VCC_8") (pintype "power_in"))
      (node (ref "IC4") (pin "1") (pinfunction "VCC_1") (pintype "power_in"))
      (node (ref "IC6") (pin "8") (pinfunction "VCC_8") (pintype "power_in"))
    )
    (net (code "66") (name "P3V3_MP") (class "Default")
      (node (ref "C100") (pin "2") (pinfunction "2_2") (pintype "passive"))
      (node (ref "C65") (pin "2") (pinfunction "2_2") (pintype "passive"))
      (node (ref "C75") (pin "2") (pinfunction "2_2") (pintype "passive"))
      (node (ref "C76") (pin "2") (pinfunction "2_2") (pintype "passive"))
      (node (ref "D12") (pin "1") (pinfunction "C_1") (pintype "passive"))
      (node (ref "D6") (pin "4") (pinfunction "VCC_4") (pintype "power_in"))
      (node (ref "IC16") (pin "4") (pinfunction "VCC_4") (pintype "power_in"))
      (node (ref "IC26") (pin "8") (pinfunction "+VS_8") (pintype "power_in"))
      (node (ref "IC27") (pin "7") (pinfunction "A0_7") (pintype "input"))
      (node (ref "IC27") (pin "8") (pinfunction "+VS_8") (pintype "power_in"))
      (node (ref "IC32") (pin "14") (pinfunction "VCC_14") (pintype "power_in"))
      (node (ref "J9") (pin "30") (pinfunction "30_30") (pintype "bidirectional"))
      (node (ref "R61") (pin "1") (pinfunction "1_1") (pintype "passive"))
    )
    (net (code "67") (name "P12V0") (class "Default")
      (node (ref "C99") (pin "2") (pinfunction "2_2") (pintype "passive"))
      (node (ref "J9") (pin "28") (pinfunction "28_28") (pintype "bidirectional"))
      (node (ref "J9") (pin "29") (pinfunction "29_29") (pintype "bidirectional"))
      (node (ref "R51") (pin "2") (pinfunction "2_2") (pintype "passive"))
      (node (ref "T13") (pin "1") (pinfunction "S_1") (pintype "passive"))
      (node (ref "T13") (pin "2") (pinfunction "S_2") (pintype "passive"))
      (node (ref "T13") (pin "3") (pinfunction "S_3") (pintype "passive"))
    )
    (net (code "68") (name "P12V0_SW") (class "Default")
      (node (ref "T13") (pin "5") (pinfunction "D_5") (pintype "passive"))
      (node (ref "T13") (pin "6") (pinfunction "D_6") (pintype "passive"))
      (node (ref "T13") (pin "7") (pinfunction "D_7") (pintype "passive"))
      (node (ref "T13") (pin "8") (pinfunction "D_8") (pintype "passive"))
    )
    (net (code "69") (name "unconnected-(IC4-DIN2RIN--Pad3)") (class "Default")
      (node (ref "IC4") (pin "3") (pinfunction "DIN2RIN-_3") (pintype "input+no_connect"))
    )
    (net (code "70") (name "unconnected-(IC4-DOUT+-Pad6)") (class "Default")
      (node (ref "IC4") (pin "6") (pinfunction "DOUT+_6") (pintype "output+no_connect"))
    )
    (net (code "71") (name "unconnected-(IC4-DOUT--Pad5)") (class "Default")
      (node (ref "IC4") (pin "5") (pinfunction "DOUT-_5") (pintype "output+no_connect"))
    )
    (net (code "72") (name "unconnected-(IC13-RIN2+-Pad3)") (class "Default")
      (node (ref "IC13") (pin "3") (pinfunction "RIN2+_3") (pintype "input+no_connect"))
    )
    (net (code "73") (name "unconnected-(IC13-RIN2--Pad4)") (class "Default")
      (node (ref "IC13") (pin "4") (pinfunction "RIN2-_4") (pintype "input+no_connect"))
    )
    (net (code "74") (name "unconnected-(IC13-ROUT2-Pad6)") (class "Default")
      (node (ref "IC13") (pin "6") (pinfunction "ROUT2_6") (pintype "output+no_connect"))
    )
    (net (code "75") (name "unconnected-(IC16-NC-Pad5)") (class "Default")
      (node (ref "IC16") (pin "5") (pinfunction "NC_5") (pintype "passive"))
    )
  )
)
